# X15-DataConversion.net
KiCad netlist of a schematic drawn in EAGLE
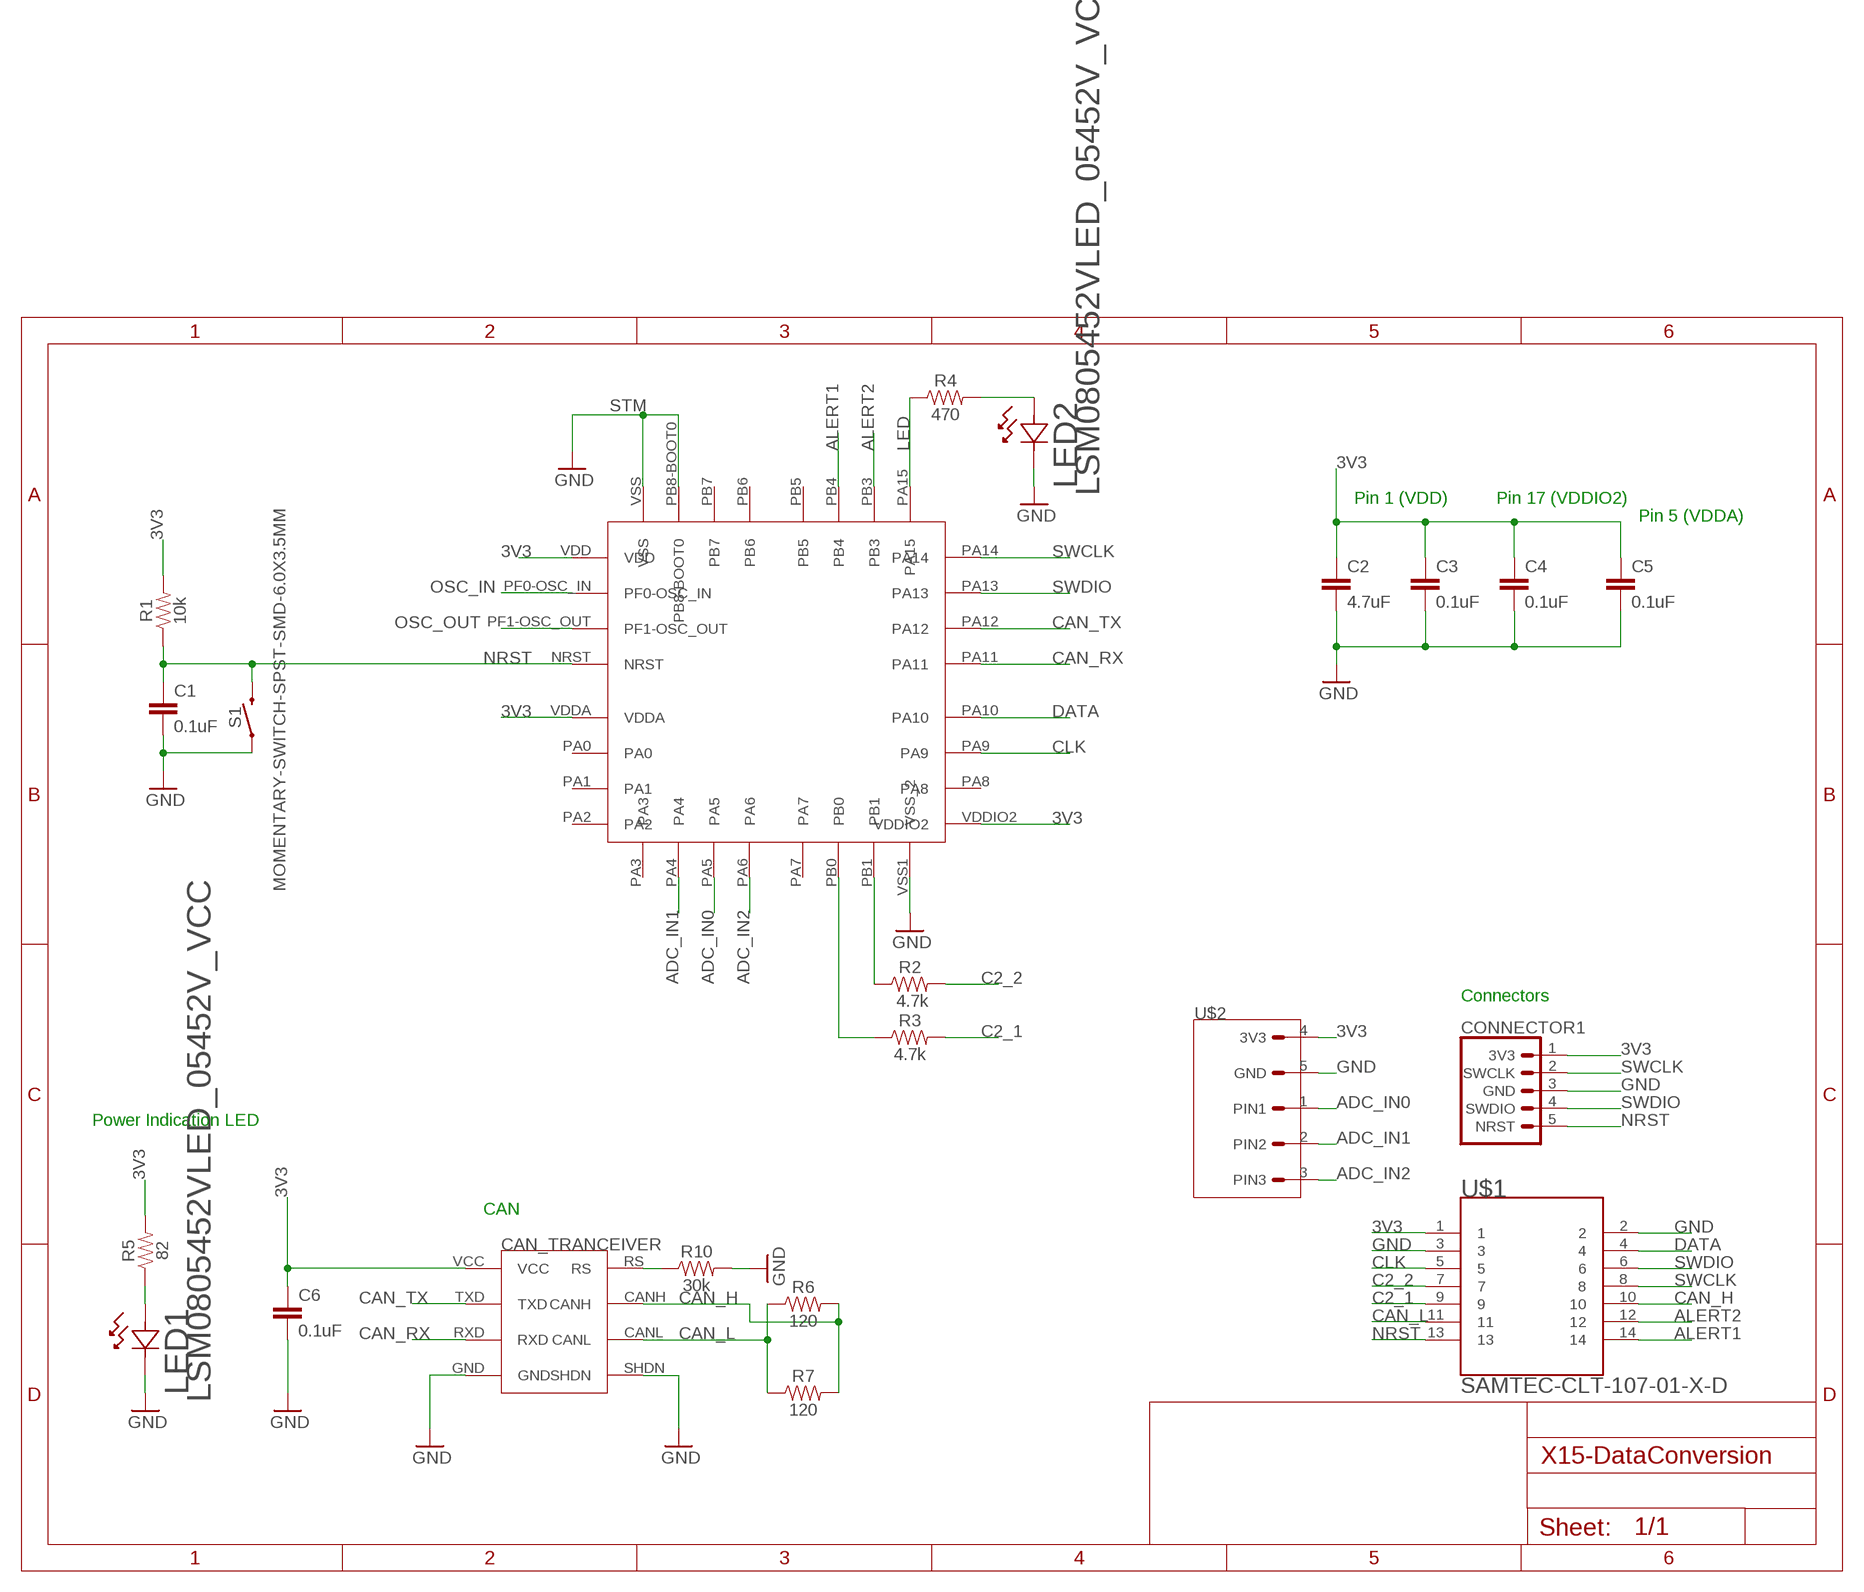
[diagram p0: schematic, sheet 1]

(export (version "E")
  (design (tool "Eeschema 10.0.6"))
  (components
    (comp (ref "C1")
      (value "0.1uF")
      (footprint "eagle-import:0603")
      (libsource (lib "eagle-import") (part "0.1UF-0603-25V-5%"))
    )
    (comp (ref "C2")
      (value "4.7uF")
      (footprint "eagle-import:0603")
      (libsource (lib "eagle-import") (part "0.1UF-0603-25V-5%"))
    )
    (comp (ref "C3")
      (value "0.1uF")
      (footprint "eagle-import:0603")
      (libsource (lib "eagle-import") (part "0.1UF-0603-25V-5%"))
    )
    (comp (ref "C4")
      (value "0.1uF")
      (footprint "eagle-import:0603")
      (libsource (lib "eagle-import") (part "0.1UF-0603-25V-5%"))
    )
    (comp (ref "C5")
      (value "0.1uF")
      (footprint "eagle-import:0603")
      (libsource (lib "eagle-import") (part "0.1UF-0603-25V-5%"))
    )
    (comp (ref "C6")
      (value "0.1uF")
      (footprint "eagle-import:0603")
      (libsource (lib "eagle-import") (part "0.1UF-0603-25V-5%"))
    )
    (comp (ref "CAN_TRANCEIVER")
      (value "MAX3058ASA+")
      (footprint "eagle-import:MAX3058ASA+")
      (libsource (lib "eagle-import") (part "MAX3058ASA+"))
    )
    (comp (ref "CONNECTOR1")
      (value "3V3 -SWCLK-GND-SWDIO- NRST")
      (footprint "eagle-import:1X05")
      (libsource (lib "eagle-import") (part "SWD_CONN"))
    )
    (comp (ref "LED1")
      (value "LSM0805452VLED_05452V_VCC")
      (footprint "eagle-import:LED_05452V_VCC")
      (fields
        (field (name "MANUFACTURER_PART_NUMBER") "LSM0805452V")
        (field (name "COPYRIGHT") "Copyright (C) 2022 Ultra Librarian. All rights reserved.")
      )
      (libsource (lib "eagle-import") (part "LSM0805452VLED_05452V_VCC"))
    )
    (comp (ref "LED2")
      (value "LSM0805452VLED_05452V_VCC")
      (footprint "eagle-import:LED_05452V_VCC")
      (fields
        (field (name "MANUFACTURER_PART_NUMBER") "LSM0805452V")
        (field (name "COPYRIGHT") "Copyright (C) 2022 Ultra Librarian. All rights reserved.")
      )
      (libsource (lib "eagle-import") (part "LSM0805452VLED_05452V_VCC"))
    )
    (comp (ref "R1")
      (value "10k")
      (footprint "eagle-import:0603")
      (libsource (lib "eagle-import") (part "RESISTOR0603"))
    )
    (comp (ref "R2")
      (value "4.7k")
      (footprint "eagle-import:0603")
      (libsource (lib "eagle-import") (part "RESISTOR0603"))
    )
    (comp (ref "R3")
      (value "4.7k")
      (footprint "eagle-import:0603")
      (libsource (lib "eagle-import") (part "RESISTOR0603"))
    )
    (comp (ref "R4")
      (value "470")
      (footprint "eagle-import:0603")
      (libsource (lib "eagle-import") (part "RESISTOR0603"))
    )
    (comp (ref "R5")
      (value "82")
      (footprint "eagle-import:0603")
      (libsource (lib "eagle-import") (part "RESISTOR0603"))
    )
    (comp (ref "R6")
      (value "120")
      (footprint "eagle-import:0603")
      (libsource (lib "eagle-import") (part "RESISTOR0603"))
    )
    (comp (ref "R7")
      (value "120")
      (footprint "eagle-import:0603")
      (libsource (lib "eagle-import") (part "RESISTOR0603"))
    )
    (comp (ref "R10")
      (value "30k")
      (footprint "eagle-import:0603")
      (libsource (lib "eagle-import") (part "RESISTOR0603"))
    )
    (comp (ref "S1")
      (value "MOMENTARY-SWITCH-SPST-SMD-6.0X3.5MM")
      (footprint "eagle-import:TACTILE_SWITCH_SMD_6.0X3.5MM")
      (libsource (lib "eagle-import") (part "MOMENTARY-SWITCH-SPST-SMD-6.0X3.5MM"))
    )
    (comp (ref "STM")
      (value "STM32F042K6T6")
      (footprint "eagle-import:STM32F042K6T6")
      (libsource (lib "eagle-import") (part "STM32F042K6T6"))
    )
    (comp (ref "U$1")
      (value "BACKPLANE->DATACONV")
      (footprint "eagle-import:SAMTEC-CLT-107-01-X-D-BACKPLANE")
      (libsource (lib "eagle-import") (part "BACKPLANE-{gt}DATACONV"))
    )
    (comp (ref "U$2")
      (value "STM_CONN")
      (footprint "eagle-import:1X05")
      (libsource (lib "eagle-import") (part "STM_CONN"))
    )
  )
  (nets
    (net (code "1") (name "/3V3") (class "Default")
      (node (ref "C2") (pin "1") (pinfunction "1_1") (pintype "passive"))
      (node (ref "C3") (pin "1") (pinfunction "1_1") (pintype "passive"))
      (node (ref "C4") (pin "1") (pinfunction "1_1") (pintype "passive"))
      (node (ref "C5") (pin "1") (pinfunction "1_1") (pintype "passive"))
      (node (ref "C6") (pin "1") (pinfunction "1_1") (pintype "passive"))
      (node (ref "CAN_TRANCEIVER") (pin "VCC") (pinfunction "VCC_VCC") (pintype "bidirectional"))
      (node (ref "CONNECTOR1") (pin "1") (pinfunction "3V3_1") (pintype "power_in"))
      (node (ref "R1") (pin "2") (pinfunction "2_2") (pintype "passive"))
      (node (ref "R5") (pin "2") (pinfunction "2_2") (pintype "passive"))
      (node (ref "STM") (pin "VDD") (pinfunction "VDD_VDD") (pintype "bidirectional"))
      (node (ref "STM") (pin "VDDA") (pinfunction "VDDA_VDDA") (pintype "bidirectional"))
      (node (ref "STM") (pin "VDDIO2") (pinfunction "VDDIO2_VDDIO2") (pintype "bidirectional"))
      (node (ref "U$1") (pin "1") (pinfunction "1_1") (pintype "passive"))
      (node (ref "U$2") (pin "4") (pinfunction "3V3_4") (pintype "power_in"))
    )
    (net (code "2") (name "/ADC_IN0") (class "Default")
      (node (ref "STM") (pin "PA5") (pinfunction "PA5_PA5") (pintype "bidirectional"))
      (node (ref "U$2") (pin "1") (pinfunction "PIN1_1") (pintype "bidirectional"))
    )
    (net (code "3") (name "/ADC_IN1") (class "Default")
      (node (ref "STM") (pin "PA4") (pinfunction "PA4_PA4") (pintype "bidirectional"))
      (node (ref "U$2") (pin "2") (pinfunction "PIN2_2") (pintype "bidirectional"))
    )
    (net (code "4") (name "/ADC_IN2") (class "Default")
      (node (ref "STM") (pin "PA6") (pinfunction "PA6_PA6") (pintype "bidirectional"))
      (node (ref "U$2") (pin "3") (pinfunction "PIN3_3") (pintype "bidirectional"))
    )
    (net (code "5") (name "/ALERT1") (class "Default")
      (node (ref "STM") (pin "PB4") (pinfunction "PB4_PB4") (pintype "bidirectional"))
      (node (ref "U$1") (pin "14") (pinfunction "14_14") (pintype "passive"))
    )
    (net (code "6") (name "/ALERT2") (class "Default")
      (node (ref "STM") (pin "PB3") (pinfunction "PB3_PB3") (pintype "bidirectional"))
      (node (ref "U$1") (pin "12") (pinfunction "12_12") (pintype "passive"))
    )
    (net (code "7") (name "/C2_1") (class "Default")
      (node (ref "R3") (pin "2") (pinfunction "2_2") (pintype "passive"))
      (node (ref "U$1") (pin "9") (pinfunction "9_9") (pintype "passive"))
    )
    (net (code "8") (name "/C2_2") (class "Default")
      (node (ref "R2") (pin "2") (pinfunction "2_2") (pintype "passive"))
      (node (ref "U$1") (pin "7") (pinfunction "7_7") (pintype "passive"))
    )
    (net (code "9") (name "/CAN_H") (class "Default")
      (node (ref "CAN_TRANCEIVER") (pin "CANH") (pinfunction "CANH_CANH") (pintype "bidirectional"))
      (node (ref "R6") (pin "2") (pinfunction "2_2") (pintype "passive"))
      (node (ref "R7") (pin "2") (pinfunction "2_2") (pintype "passive"))
      (node (ref "U$1") (pin "10") (pinfunction "10_10") (pintype "passive"))
    )
    (net (code "10") (name "/CAN_L") (class "Default")
      (node (ref "CAN_TRANCEIVER") (pin "CANL") (pinfunction "CANL_CANL") (pintype "bidirectional"))
      (node (ref "R6") (pin "1") (pinfunction "1_1") (pintype "passive"))
      (node (ref "R7") (pin "1") (pinfunction "1_1") (pintype "passive"))
      (node (ref "U$1") (pin "11") (pinfunction "11_11") (pintype "passive"))
    )
    (net (code "11") (name "/CAN_RX") (class "Default")
      (node (ref "CAN_TRANCEIVER") (pin "RXD") (pinfunction "RXD_RXD") (pintype "bidirectional"))
      (node (ref "STM") (pin "PA11") (pinfunction "PA11_PA11") (pintype "bidirectional"))
    )
    (net (code "12") (name "/CAN_TX") (class "Default")
      (node (ref "CAN_TRANCEIVER") (pin "TXD") (pinfunction "TXD_TXD") (pintype "bidirectional"))
      (node (ref "STM") (pin "PA12") (pinfunction "PA12_PA12") (pintype "bidirectional"))
    )
    (net (code "13") (name "/CLK") (class "Default")
      (node (ref "STM") (pin "PA9") (pinfunction "PA9_PA9") (pintype "bidirectional"))
      (node (ref "U$1") (pin "5") (pinfunction "5_5") (pintype "passive"))
    )
    (net (code "14") (name "/DATA") (class "Default")
      (node (ref "STM") (pin "PA10") (pinfunction "PA10_PA10") (pintype "bidirectional"))
      (node (ref "U$1") (pin "4") (pinfunction "4_4") (pintype "passive"))
    )
    (net (code "15") (name "/LED") (class "Default")
      (node (ref "R4") (pin "1") (pinfunction "1_1") (pintype "passive"))
      (node (ref "STM") (pin "PA15") (pinfunction "PA15_PA15") (pintype "bidirectional"))
    )
    (net (code "16") (name "/NRST") (class "Default")
      (node (ref "C1") (pin "1") (pinfunction "1_1") (pintype "passive"))
      (node (ref "CONNECTOR1") (pin "5") (pinfunction "NRST_5") (pintype "open_collector"))
      (node (ref "R1") (pin "1") (pinfunction "1_1") (pintype "passive"))
      (node (ref "S1") (pin "2") (pinfunction "2_2") (pintype "passive"))
      (node (ref "STM") (pin "NRST") (pinfunction "NRST_NRST") (pintype "bidirectional"))
      (node (ref "U$1") (pin "13") (pinfunction "13_13") (pintype "passive"))
    )
    (net (code "17") (name "/OSC_IN") (class "Default")
      (node (ref "STM") (pin "PF0-OSC_IN") (pinfunction "PF0-OSC_IN_PF0-OSC_IN") (pintype "bidirectional"))
    )
    (net (code "18") (name "/OSC_OUT") (class "Default")
      (node (ref "STM") (pin "PF1-OSC_OUT") (pinfunction "PF1-OSC_OUT_PF1-OSC_OUT") (pintype "bidirectional"))
    )
    (net (code "19") (name "/SWCLK") (class "Default")
      (node (ref "CONNECTOR1") (pin "2") (pinfunction "SWCLK_2") (pintype "input"))
      (node (ref "STM") (pin "PA14") (pinfunction "PA14_PA14") (pintype "bidirectional"))
      (node (ref "U$1") (pin "8") (pinfunction "8_8") (pintype "passive"))
    )
    (net (code "20") (name "/SWDIO") (class "Default")
      (node (ref "CONNECTOR1") (pin "4") (pinfunction "SWDIO_4") (pintype "bidirectional"))
      (node (ref "STM") (pin "PA13") (pinfunction "PA13_PA13") (pintype "bidirectional"))
      (node (ref "U$1") (pin "6") (pinfunction "6_6") (pintype "passive"))
    )
    (net (code "21") (name "GND") (class "Default")
      (node (ref "C1") (pin "2") (pinfunction "2_2") (pintype "passive"))
      (node (ref "C2") (pin "2") (pinfunction "2_2") (pintype "passive"))
      (node (ref "C3") (pin "2") (pinfunction "2_2") (pintype "passive"))
      (node (ref "C4") (pin "2") (pinfunction "2_2") (pintype "passive"))
      (node (ref "C5") (pin "2") (pinfunction "2_2") (pintype "passive"))
      (node (ref "C6") (pin "2") (pinfunction "2_2") (pintype "passive"))
      (node (ref "CAN_TRANCEIVER") (pin "GND") (pinfunction "GND_GND") (pintype "bidirectional"))
      (node (ref "CAN_TRANCEIVER") (pin "SHDN") (pinfunction "SHDN_SHDN") (pintype "bidirectional"))
      (node (ref "CONNECTOR1") (pin "3") (pinfunction "GND_3") (pintype "power_in"))
      (node (ref "LED1") (pin "2") (pinfunction "2_2") (pintype "passive"))
      (node (ref "LED2") (pin "2") (pinfunction "2_2") (pintype "passive"))
      (node (ref "R10") (pin "2") (pinfunction "2_2") (pintype "passive"))
      (node (ref "S1") (pin "1") (pinfunction "1_1") (pintype "passive"))
      (node (ref "STM") (pin "PB8-BOOT0") (pinfunction "PB8-BOOT0_PB8-BOOT0") (pintype "bidirectional"))
      (node (ref "STM") (pin "VSS") (pinfunction "VSS_VSS") (pintype "bidirectional"))
      (node (ref "STM") (pin "VSS1") (pinfunction "VSS_2_VSS1") (pintype "bidirectional"))
      (node (ref "U$1") (pin "2") (pinfunction "2_2") (pintype "passive"))
      (node (ref "U$1") (pin "3") (pinfunction "3_3") (pintype "passive"))
      (node (ref "U$2") (pin "5") (pinfunction "GND_5") (pintype "power_in"))
    )
    (net (code "22") (name "Net-(CAN_TRANCEIVER-PadRS)") (class "Default")
      (node (ref "CAN_TRANCEIVER") (pin "RS") (pinfunction "RS_RS") (pintype "bidirectional"))
      (node (ref "R10") (pin "1") (pinfunction "1_1") (pintype "passive"))
    )
    (net (code "23") (name "Net-(LED1-Pad1)") (class "Default")
      (node (ref "LED1") (pin "1") (pinfunction "1_1") (pintype "passive"))
      (node (ref "R5") (pin "1") (pinfunction "1_1") (pintype "passive"))
    )
    (net (code "24") (name "Net-(LED2-Pad1)") (class "Default")
      (node (ref "LED2") (pin "1") (pinfunction "1_1") (pintype "passive"))
      (node (ref "R4") (pin "2") (pinfunction "2_2") (pintype "passive"))
    )
    (net (code "25") (name "Net-(R2-Pad1)") (class "Default")
      (node (ref "R2") (pin "1") (pinfunction "1_1") (pintype "passive"))
      (node (ref "STM") (pin "PB1") (pinfunction "PB1_PB1") (pintype "bidirectional"))
    )
    (net (code "26") (name "Net-(R3-Pad1)") (class "Default")
      (node (ref "R3") (pin "1") (pinfunction "1_1") (pintype "passive"))
      (node (ref "STM") (pin "PB0") (pinfunction "PB0_PB0") (pintype "bidirectional"))
    )
    (net (code "27") (name "unconnected-(STM-PadPA0)") (class "Default")
      (node (ref "STM") (pin "PA0") (pinfunction "PA0_PA0") (pintype "bidirectional"))
    )
    (net (code "28") (name "unconnected-(STM-PadPA1)") (class "Default")
      (node (ref "STM") (pin "PA1") (pinfunction "PA1_PA1") (pintype "bidirectional"))
    )
    (net (code "29") (name "unconnected-(STM-PadPA2)") (class "Default")
      (node (ref "STM") (pin "PA2") (pinfunction "PA2_PA2") (pintype "bidirectional"))
    )
    (net (code "30") (name "unconnected-(STM-PadPA3)") (class "Default")
      (node (ref "STM") (pin "PA3") (pinfunction "PA3_PA3") (pintype "bidirectional"))
    )
    (net (code "31") (name "unconnected-(STM-PadPA7)") (class "Default")
      (node (ref "STM") (pin "PA7") (pinfunction "PA7_PA7") (pintype "bidirectional"))
    )
    (net (code "32") (name "unconnected-(STM-PadPA8)") (class "Default")
      (node (ref "STM") (pin "PA8") (pinfunction "PA8_PA8") (pintype "bidirectional"))
    )
    (net (code "33") (name "unconnected-(STM-PadPB5)") (class "Default")
      (node (ref "STM") (pin "PB5") (pinfunction "PB5_PB5") (pintype "bidirectional"))
    )
    (net (code "34") (name "unconnected-(STM-PadPB6)") (class "Default")
      (node (ref "STM") (pin "PB6") (pinfunction "PB6_PB6") (pintype "bidirectional"))
    )
    (net (code "35") (name "unconnected-(STM-PadPB7)") (class "Default")
      (node (ref "STM") (pin "PB7") (pinfunction "PB7_PB7") (pintype "bidirectional"))
    )
  )
)
